# detector_t85-pu.net
KiCad netlist of a schematic drawn in EAGLE
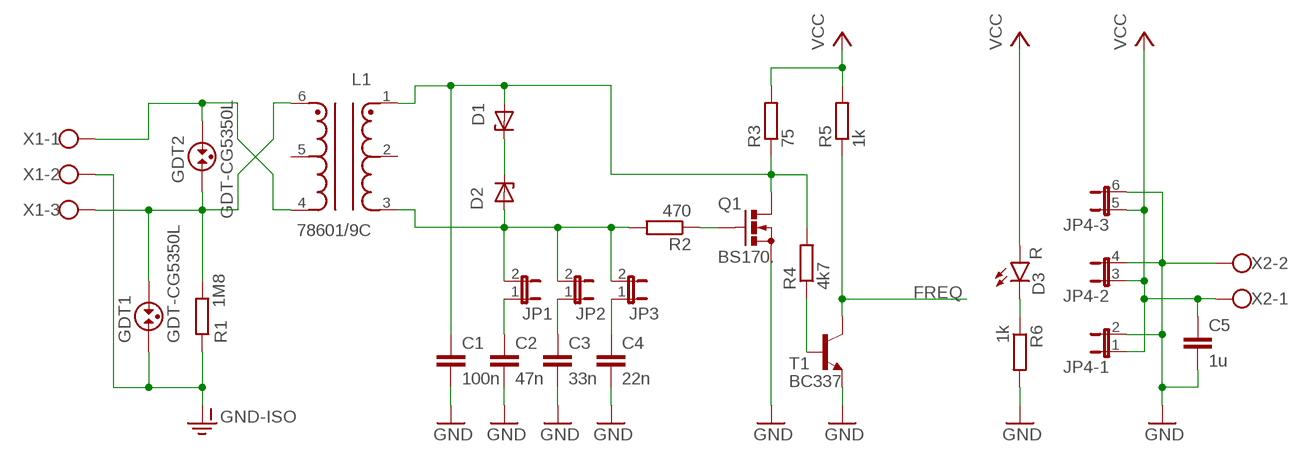
[diagram p0: schematic, sheet 1]
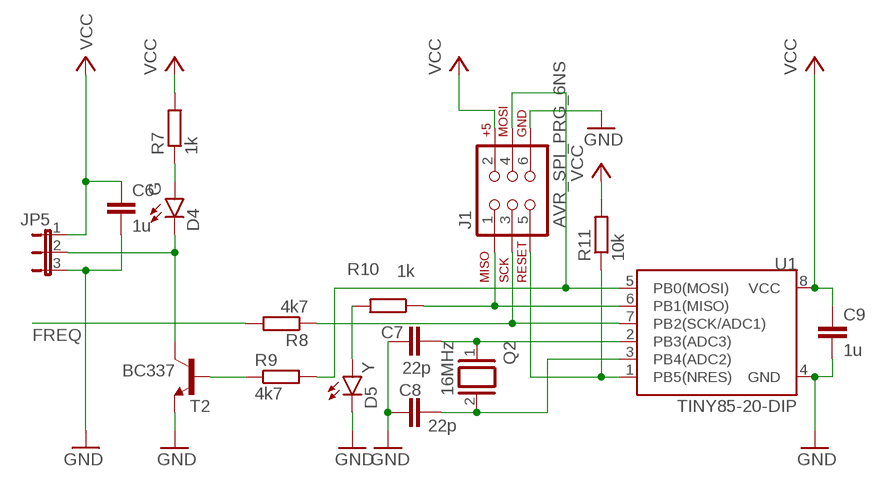
[diagram p1: schematic, sheet 2]

(export (version "E")
  (design (tool "Eeschema 10.0.6"))
  (components
    (comp (ref "C6")
      (value "1u")
      (footprint "eagle-import:C050-025X075")
      (libsource (lib "eagle-import") (part "C-EU050-025X075"))
    )
    (comp (ref "C7")
      (value "22p")
      (footprint "eagle-import:CAP-PTH-SMALL2")
      (libsource (lib "eagle-import") (part "CAPPTH2"))
    )
    (comp (ref "C8")
      (value "22p")
      (footprint "eagle-import:CAP-PTH-SMALL2")
      (libsource (lib "eagle-import") (part "CAPPTH2"))
    )
    (comp (ref "C9")
      (value "1u")
      (footprint "eagle-import:C050-025X075")
      (libsource (lib "eagle-import") (part "C-EU050-025X075"))
    )
    (comp (ref "D4")
      (value "G")
      (footprint "eagle-import:LED3MM")
      (libsource (lib "eagle-import") (part "LED3MM"))
    )
    (comp (ref "D5")
      (value "Y")
      (footprint "eagle-import:LED3MM")
      (libsource (lib "eagle-import") (part "LED3MM"))
    )
    (comp (ref "J1")
      (value "AVR_SPI_PRG_6NS")
      (footprint "eagle-import:2X3-NS")
      (libsource (lib "eagle-import") (part "AVR_SPI_PRG_6NS"))
    )
    (comp (ref "JP5")
      (value "JP2E")
      (footprint "eagle-import:JP2")
      (libsource (lib "eagle-import") (part "JP2E"))
    )
    (comp (ref "Q2")
      (value "16MHz")
      (footprint "eagle-import:QS")
      (libsource (lib "eagle-import") (part "XTAL/S"))
    )
    (comp (ref "R7")
      (value "1k")
      (footprint "eagle-import:0204_5")
      (libsource (lib "eagle-import") (part "R-EU_0204/5"))
    )
    (comp (ref "R8")
      (value "4k7")
      (footprint "eagle-import:0204_5")
      (libsource (lib "eagle-import") (part "R-EU_0204/5"))
    )
    (comp (ref "R9")
      (value "4k7")
      (footprint "eagle-import:0204_5")
      (libsource (lib "eagle-import") (part "R-EU_0204/5"))
    )
    (comp (ref "R10")
      (value "1k")
      (footprint "eagle-import:0204_5")
      (libsource (lib "eagle-import") (part "R-EU_0204/5"))
    )
    (comp (ref "R11")
      (value "10k")
      (footprint "eagle-import:0204_5")
      (libsource (lib "eagle-import") (part "R-EU_0204/5"))
    )
    (comp (ref "T2")
      (value "BC337")
      (footprint "eagle-import:TO92-CBE")
      (libsource (lib "eagle-import") (part "-NPN-TO92-CBEBC337"))
    )
    (comp (ref "U1")
      (value "TINY85-20-DIP")
      (footprint "eagle-import:DIP08")
      (libsource (lib "eagle-import") (part "ATTINY45TINY45-20-DIP"))
    )
    (comp (ref "C1")
      (value "100n")
      (footprint "eagle-import:C050-024X044")
      (libsource (lib "eagle-import") (part "resistor_C-EU050-024X044"))
    )
    (comp (ref "C2")
      (value "47n")
      (footprint "eagle-import:C050-024X044")
      (libsource (lib "eagle-import") (part "resistor_C-EU050-024X044"))
    )
    (comp (ref "C3")
      (value "33n")
      (footprint "eagle-import:C050-024X044")
      (libsource (lib "eagle-import") (part "resistor_C-EU050-024X044"))
    )
    (comp (ref "C4")
      (value "22n")
      (footprint "eagle-import:C050-024X044")
      (libsource (lib "eagle-import") (part "resistor_C-EU050-024X044"))
    )
    (comp (ref "C5")
      (value "1u")
      (footprint "eagle-import:C050-025X075")
      (libsource (lib "eagle-import") (part "C-EU050-025X075"))
    )
    (comp (ref "D1")
      (value "24V")
      (footprint "eagle-import:ZDIO-5")
      (libsource (lib "eagle-import") (part "ZENER-DIODEZD-5"))
    )
    (comp (ref "D2")
      (value "24V")
      (footprint "eagle-import:ZDIO-5")
      (libsource (lib "eagle-import") (part "ZENER-DIODEZD-5"))
    )
    (comp (ref "D3")
      (value "R")
      (footprint "eagle-import:LED3MM")
      (libsource (lib "eagle-import") (part "LED3MM"))
    )
    (comp (ref "GDT1")
      (value "GDT-CG5350L")
      (footprint "eagle-import:CG5350L")
      (libsource (lib "eagle-import") (part "GDT-CG5350L"))
    )
    (comp (ref "GDT2")
      (value "GDT-CG5350L")
      (footprint "eagle-import:CG5350L")
      (libsource (lib "eagle-import") (part "GDT-CG5350L"))
    )
    (comp (ref "JP1")
      (value "JUMPER-2PTH")
      (footprint "eagle-import:1X02")
      (libsource (lib "eagle-import") (part "JUMPER-2PTH"))
    )
    (comp (ref "JP2")
      (value "JUMPER-2PTH")
      (footprint "eagle-import:1X02")
      (libsource (lib "eagle-import") (part "JUMPER-2PTH"))
    )
    (comp (ref "JP3")
      (value "JUMPER-2PTH")
      (footprint "eagle-import:1X02")
      (libsource (lib "eagle-import") (part "JUMPER-2PTH"))
    )
    (comp (ref "JP4")
      (value "JP3QE")
      (footprint "eagle-import:JP3Q")
      (libsource (lib "eagle-import") (part "JP3QE"))
    )
    (comp (ref "L1")
      (value "78601/9C")
      (footprint "eagle-import:78601_9C")
      (libsource (lib "eagle-import") (part "78601/9C"))
    )
    (comp (ref "Q1")
      (value "BS170.")
      (footprint "eagle-import:TO92-DGS")
      (libsource (lib "eagle-import") (part "BS170."))
    )
    (comp (ref "R1")
      (value "1M8")
      (footprint "eagle-import:0204_5")
      (libsource (lib "eagle-import") (part "R-EU_0204/5"))
    )
    (comp (ref "R2")
      (value "470")
      (footprint "eagle-import:0204_5")
      (libsource (lib "eagle-import") (part "R-EU_0204/5"))
    )
    (comp (ref "R3")
      (value "75")
      (footprint "eagle-import:0204_7")
      (libsource (lib "eagle-import") (part "R-EU_0204/7"))
    )
    (comp (ref "R4")
      (value "4k7")
      (footprint "eagle-import:0204_5")
      (libsource (lib "eagle-import") (part "R-EU_0204/5"))
    )
    (comp (ref "R5")
      (value "1k")
      (footprint "eagle-import:0204_5")
      (libsource (lib "eagle-import") (part "R-EU_0204/5"))
    )
    (comp (ref "R6")
      (value "1k")
      (footprint "eagle-import:0204_5")
      (libsource (lib "eagle-import") (part "R-EU_0204/5"))
    )
    (comp (ref "T1")
      (value "BC337")
      (footprint "eagle-import:TO92-CBE")
      (libsource (lib "eagle-import") (part "-NPN-TO92-CBEBC337"))
    )
    (comp (ref "X1")
      (value "W237-103")
      (footprint "eagle-import:W237-103")
      (fields (field (name "MPN") "237-103"))
      (libsource (lib "eagle-import") (part "W237-103"))
    )
    (comp (ref "X2")
      (value "W237-102")
      (footprint "eagle-import:W237-102")
      (fields (field (name "MPN") "237-102"))
      (libsource (lib "eagle-import") (part "W237-102"))
    )
  )
  (nets
    (net (code "1") (name "FREQ") (class "Default")
      (node (ref "R5") (pin "1") (pinfunction "1_1") (pintype "passive"))
      (node (ref "R8") (pin "2") (pinfunction "2_2") (pintype "passive"))
      (node (ref "T1") (pin "C") (pinfunction "C_C") (pintype "passive"))
    )
    (net (code "2") (name "GND") (class "Default")
      (node (ref "C1") (pin "2") (pinfunction "2_2") (pintype "passive"))
      (node (ref "C2") (pin "2") (pinfunction "2_2") (pintype "passive"))
      (node (ref "C3") (pin "2") (pinfunction "2_2") (pintype "passive"))
      (node (ref "C4") (pin "2") (pinfunction "2_2") (pintype "passive"))
      (node (ref "C5") (pin "2") (pinfunction "2_2") (pintype "passive"))
      (node (ref "C6") (pin "2") (pinfunction "2_2") (pintype "passive"))
      (node (ref "C7") (pin "1") (pinfunction "1_1") (pintype "passive"))
      (node (ref "C8") (pin "1") (pinfunction "1_1") (pintype "passive"))
      (node (ref "C9") (pin "2") (pinfunction "2_2") (pintype "passive"))
      (node (ref "D5") (pin "K") (pinfunction "C_K") (pintype "passive"))
      (node (ref "J1") (pin "6") (pinfunction "6_6") (pintype "passive"))
      (node (ref "JP4") (pin "2") (pinfunction "2_2") (pintype "passive"))
      (node (ref "JP4") (pin "4") (pinfunction "2_4") (pintype "passive"))
      (node (ref "JP4") (pin "6") (pinfunction "2_6") (pintype "passive"))
      (node (ref "JP5") (pin "3") (pinfunction "3_3") (pintype "passive"))
      (node (ref "Q1") (pin "S") (pinfunction "S_S") (pintype "passive"))
      (node (ref "R6") (pin "2") (pinfunction "2_2") (pintype "passive"))
      (node (ref "T1") (pin "E") (pinfunction "E_E") (pintype "passive"))
      (node (ref "T2") (pin "E") (pinfunction "E_E") (pintype "passive"))
      (node (ref "U1") (pin "4") (pinfunction "GND_4") (pintype "bidirectional"))
      (node (ref "X2") (pin "2") (pinfunction "KL_2") (pintype "passive"))
    )
    (net (code "3") (name "GND-ISO") (class "Default")
      (node (ref "GDT1") (pin "1") (pinfunction "1_1") (pintype "passive"))
      (node (ref "R1") (pin "1") (pinfunction "1_1") (pintype "passive"))
      (node (ref "X1") (pin "2") (pinfunction "KL_2") (pintype "passive"))
    )
    (net (code "4") (name "Net-(C1-Pad1)") (class "Default")
      (node (ref "C1") (pin "1") (pinfunction "1_1") (pintype "passive"))
      (node (ref "D1") (pin "A") (pinfunction "A_A") (pintype "passive"))
      (node (ref "L1") (pin "1") (pinfunction "1_1") (pintype "passive"))
      (node (ref "Q1") (pin "D") (pinfunction "D_D") (pintype "passive"))
      (node (ref "R3") (pin "1") (pinfunction "1_1") (pintype "passive"))
      (node (ref "R4") (pin "2") (pinfunction "2_2") (pintype "passive"))
    )
    (net (code "5") (name "Net-(C2-Pad1)") (class "Default")
      (node (ref "C2") (pin "1") (pinfunction "1_1") (pintype "passive"))
      (node (ref "JP1") (pin "1") (pinfunction "1_1") (pintype "passive"))
    )
    (net (code "6") (name "Net-(C3-Pad1)") (class "Default")
      (node (ref "C3") (pin "1") (pinfunction "1_1") (pintype "passive"))
      (node (ref "JP2") (pin "1") (pinfunction "1_1") (pintype "passive"))
    )
    (net (code "7") (name "Net-(C4-Pad1)") (class "Default")
      (node (ref "C4") (pin "1") (pinfunction "1_1") (pintype "passive"))
      (node (ref "JP3") (pin "1") (pinfunction "1_1") (pintype "passive"))
    )
    (net (code "8") (name "Net-(D1-PadC)") (class "Default")
      (node (ref "D1") (pin "C") (pinfunction "C_C") (pintype "passive"))
      (node (ref "D2") (pin "C") (pinfunction "C_C") (pintype "passive"))
    )
    (net (code "9") (name "Net-(D2-PadA)") (class "Default")
      (node (ref "D2") (pin "A") (pinfunction "A_A") (pintype "passive"))
      (node (ref "JP1") (pin "2") (pinfunction "2_2") (pintype "passive"))
      (node (ref "JP2") (pin "2") (pinfunction "2_2") (pintype "passive"))
      (node (ref "JP3") (pin "2") (pinfunction "2_2") (pintype "passive"))
      (node (ref "L1") (pin "3") (pinfunction "3_3") (pintype "passive"))
      (node (ref "R2") (pin "2") (pinfunction "2_2") (pintype "passive"))
    )
    (net (code "10") (name "Net-(D3-C)") (class "Default")
      (node (ref "D3") (pin "K") (pinfunction "C_K") (pintype "passive"))
      (node (ref "R6") (pin "1") (pinfunction "1_1") (pintype "passive"))
    )
    (net (code "11") (name "Net-(D4-C)") (class "Default")
      (node (ref "D4") (pin "K") (pinfunction "C_K") (pintype "passive"))
      (node (ref "JP5") (pin "2") (pinfunction "2_2") (pintype "passive"))
      (node (ref "T2") (pin "C") (pinfunction "C_C") (pintype "passive"))
    )
    (net (code "12") (name "Net-(D4-PadA)") (class "Default")
      (node (ref "D4") (pin "A") (pinfunction "A_A") (pintype "passive"))
      (node (ref "R7") (pin "1") (pinfunction "1_1") (pintype "passive"))
    )
    (net (code "13") (name "Net-(D5-PadA)") (class "Default")
      (node (ref "D5") (pin "A") (pinfunction "A_A") (pintype "passive"))
      (node (ref "R10") (pin "2") (pinfunction "2_2") (pintype "passive"))
    )
    (net (code "14") (name "Net-(Q1-PadG)") (class "Default")
      (node (ref "Q1") (pin "G") (pinfunction "G_G") (pintype "passive"))
      (node (ref "R2") (pin "1") (pinfunction "1_1") (pintype "passive"))
    )
    (net (code "15") (name "Net-(R4-Pad1)") (class "Default")
      (node (ref "R4") (pin "1") (pinfunction "1_1") (pintype "passive"))
      (node (ref "T1") (pin "B") (pinfunction "B_B") (pintype "passive"))
    )
    (net (code "16") (name "Net-(R9-Pad1)") (class "Default")
      (node (ref "R9") (pin "1") (pinfunction "1_1") (pintype "passive"))
      (node (ref "T2") (pin "B") (pinfunction "B_B") (pintype "passive"))
    )
    (net (code "17") (name "Net-(U1-PB0(MOSI))") (class "Default")
      (node (ref "J1") (pin "4") (pinfunction "4_4") (pintype "passive"))
      (node (ref "R9") (pin "2") (pinfunction "2_2") (pintype "passive"))
      (node (ref "U1") (pin "5") (pinfunction "PB0(MOSI)_5") (pintype "bidirectional"))
    )
    (net (code "18") (name "Net-(U1-PB1(MISO))") (class "Default")
      (node (ref "J1") (pin "1") (pinfunction "1_1") (pintype "passive"))
      (node (ref "R10") (pin "1") (pinfunction "1_1") (pintype "passive"))
      (node (ref "U1") (pin "6") (pinfunction "PB1(MISO)_6") (pintype "bidirectional"))
    )
    (net (code "19") (name "Net-(U1-PB2(SCK{slash}ADC1))") (class "Default")
      (node (ref "J1") (pin "3") (pinfunction "3_3") (pintype "passive"))
      (node (ref "R8") (pin "1") (pinfunction "1_1") (pintype "passive"))
      (node (ref "U1") (pin "7") (pinfunction "PB2(SCK/ADC1)_7") (pintype "bidirectional"))
    )
    (net (code "20") (name "Net-(U1-PB3(ADC3))") (class "Default")
      (node (ref "C7") (pin "2") (pinfunction "2_2") (pintype "passive"))
      (node (ref "Q2") (pin "1") (pinfunction "1_1") (pintype "passive"))
      (node (ref "U1") (pin "2") (pinfunction "PB3(ADC3)_2") (pintype "bidirectional"))
    )
    (net (code "21") (name "Net-(U1-PB4(ADC2))") (class "Default")
      (node (ref "C8") (pin "2") (pinfunction "2_2") (pintype "passive"))
      (node (ref "Q2") (pin "2") (pinfunction "2_2") (pintype "passive"))
      (node (ref "U1") (pin "3") (pinfunction "PB4(ADC2)_3") (pintype "bidirectional"))
    )
    (net (code "22") (name "Net-(U1-PB5(NRES))") (class "Default")
      (node (ref "J1") (pin "5") (pinfunction "5_5") (pintype "passive"))
      (node (ref "R11") (pin "1") (pinfunction "1_1") (pintype "passive"))
      (node (ref "U1") (pin "1") (pinfunction "PB5(NRES)_1") (pintype "bidirectional"))
    )
    (net (code "23") (name "Net-(X1A-KL)") (class "Default")
      (node (ref "GDT2") (pin "2") (pinfunction "2_2") (pintype "passive"))
      (node (ref "L1") (pin "4") (pinfunction "4_4") (pintype "passive"))
      (node (ref "X1") (pin "1") (pinfunction "KL_1") (pintype "passive"))
    )
    (net (code "24") (name "Net-(X1C-KL)") (class "Default")
      (node (ref "GDT1") (pin "2") (pinfunction "2_2") (pintype "passive"))
      (node (ref "GDT2") (pin "1") (pinfunction "1_1") (pintype "passive"))
      (node (ref "L1") (pin "6") (pinfunction "6_6") (pintype "passive"))
      (node (ref "R1") (pin "2") (pinfunction "2_2") (pintype "passive"))
      (node (ref "X1") (pin "3") (pinfunction "KL_3") (pintype "passive"))
    )
    (net (code "25") (name "VCC") (class "Default")
      (node (ref "C5") (pin "1") (pinfunction "1_1") (pintype "passive"))
      (node (ref "C6") (pin "1") (pinfunction "1_1") (pintype "passive"))
      (node (ref "C9") (pin "1") (pinfunction "1_1") (pintype "passive"))
      (node (ref "D3") (pin "A") (pinfunction "A_A") (pintype "passive"))
      (node (ref "J1") (pin "2") (pinfunction "2_2") (pintype "passive"))
      (node (ref "JP4") (pin "1") (pinfunction "1_1") (pintype "passive"))
      (node (ref "JP4") (pin "3") (pinfunction "1_3") (pintype "passive"))
      (node (ref "JP4") (pin "5") (pinfunction "1_5") (pintype "passive"))
      (node (ref "JP5") (pin "1") (pinfunction "1_1") (pintype "passive"))
      (node (ref "R11") (pin "2") (pinfunction "2_2") (pintype "passive"))
      (node (ref "R3") (pin "2") (pinfunction "2_2") (pintype "passive"))
      (node (ref "R5") (pin "2") (pinfunction "2_2") (pintype "passive"))
      (node (ref "R7") (pin "2") (pinfunction "2_2") (pintype "passive"))
      (node (ref "U1") (pin "8") (pinfunction "VCC_8") (pintype "bidirectional"))
      (node (ref "X2") (pin "1") (pinfunction "KL_1") (pintype "passive"))
    )
    (net (code "26") (name "unconnected-(L1-Pad2)") (class "Default")
      (node (ref "L1") (pin "2") (pinfunction "2_2") (pintype "passive"))
    )
    (net (code "27") (name "unconnected-(L1-Pad5)") (class "Default")
      (node (ref "L1") (pin "5") (pinfunction "5_5") (pintype "passive"))
    )
  )
)
